# RealTimeClock.net
KiCad netlist of a schematic drawn in Altium Designer
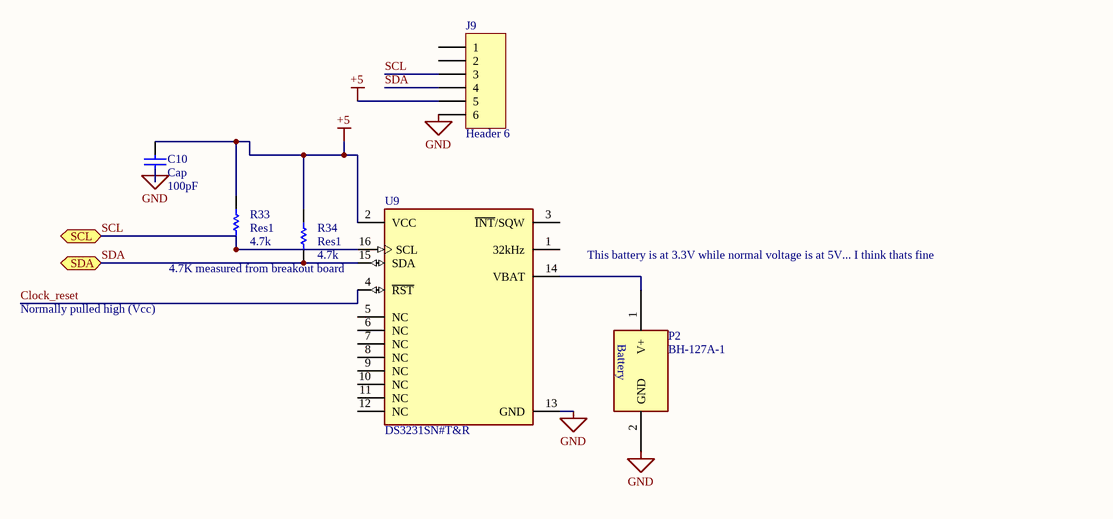
[diagram p0: RealTimeClock.SchDoc]

(export (version "E")
  (design (tool "Eeschema 10.0.6"))
  (components
    (comp (ref "C10")
      (value "Cap")
      (footprint "0603")
      (description "Capacitor")
      (fields (field (name "ALTIUM_VALUE") "100pF") (field (name "PUBLISHER") "Altium Limited"))
      (libsource (lib "Miscellaneous Devices") (part "Cap"))
    )
    (comp (ref "J9")
      (value "Header 6")
      (footprint "HDR1X6")
      (description "Header, 6-Pin")
      (fields (field (name "PUBLISHER") "Altium Limited"))
      (libsource (lib "Miscellaneous Connectors") (part "Header 6"))
    )
    (comp (ref "P2")
      (value "BH-127A-1")
      (footprint "banana")
      (libsource (lib "BH-127A-1") (part "BH-127A-1"))
    )
    (comp (ref "R33")
      (value "Res1")
      (footprint "0603")
      (description "Resistor")
      (fields (field (name "ALTIUM_VALUE") "4.7k") (field (name "PUBLISHER") "Altium Limited"))
      (libsource (lib "Miscellaneous Devices") (part "Res1"))
    )
    (comp (ref "R34")
      (value "Res1")
      (footprint "0603")
      (description "Resistor")
      (fields (field (name "ALTIUM_VALUE") "4.7k") (field (name "PUBLISHER") "Altium Limited"))
      (libsource (lib "Miscellaneous Devices") (part "Res1"))
    )
    (comp (ref "U9")
      (value "DS3231SN#T&R")
      (footprint "FP-W16-H2-MFG")
      (description "IC RTC CLK/CALENDAR I2C 16-SOIC")
      (libsource (lib "Altium Content Vault") (part "49e129a02c1e013a88f81c98964c20e"))
    )
  )
  (nets
    (net (code "1") (name "+5") (class "Default")
      (node (ref "C10") (pin "2") (pinfunction "2_2") (pintype "passive"))
      (node (ref "J9") (pin "5") (pinfunction "5_5") (pintype "passive"))
      (node (ref "R33") (pin "2") (pinfunction "2_2") (pintype "passive"))
      (node (ref "R34") (pin "2") (pinfunction "2_2") (pintype "passive"))
      (node (ref "U9") (pin "2") (pinfunction "VCC_2") (pintype "power_in"))
    )
    (net (code "2") (name "/Clock_reset") (class "Default")
      (node (ref "U9") (pin "4") (pinfunction "~{RST}_4") (pintype "bidirectional"))
    )
    (net (code "3") (name "/SCL") (class "Default")
      (node (ref "J9") (pin "3") (pinfunction "3_3") (pintype "passive"))
      (node (ref "R33") (pin "1") (pinfunction "1_1") (pintype "passive"))
      (node (ref "U9") (pin "16") (pinfunction "SCL_16") (pintype "input"))
    )
    (net (code "4") (name "/SDA") (class "Default")
      (node (ref "J9") (pin "4") (pinfunction "4_4") (pintype "passive"))
      (node (ref "R34") (pin "1") (pinfunction "1_1") (pintype "passive"))
      (node (ref "U9") (pin "15") (pinfunction "SDA_15") (pintype "bidirectional"))
    )
    (net (code "5") (name "GND") (class "Default")
      (node (ref "C10") (pin "1") (pinfunction "1_1") (pintype "passive"))
      (node (ref "J9") (pin "6") (pinfunction "6_6") (pintype "passive"))
      (node (ref "P2") (pin "2") (pinfunction "GND_2") (pintype "power_in"))
      (node (ref "U9") (pin "13") (pinfunction "GND_13") (pintype "power_in"))
    )
    (net (code "6") (name "Net-(P2-V+)") (class "Default")
      (node (ref "P2") (pin "1") (pinfunction "V+_1") (pintype "power_in"))
      (node (ref "U9") (pin "14") (pinfunction "VBAT_14") (pintype "power_in"))
    )
    (net (code "7") (name "unconnected-(J9-Pad1)") (class "Default")
      (node (ref "J9") (pin "1") (pinfunction "1_1") (pintype "passive"))
    )
    (net (code "8") (name "unconnected-(J9-Pad2)") (class "Default")
      (node (ref "J9") (pin "2") (pinfunction "2_2") (pintype "passive"))
    )
    (net (code "9") (name "unconnected-(U9-32kHz-Pad1)") (class "Default")
      (node (ref "U9") (pin "1") (pinfunction "32kHz_1") (pintype "open_collector"))
    )
    (net (code "10") (name "unconnected-(U9-NC-Pad5)") (class "Default")
      (node (ref "U9") (pin "5") (pinfunction "NC_5") (pintype "passive"))
    )
    (net (code "11") (name "unconnected-(U9-NC-Pad6)") (class "Default")
      (node (ref "U9") (pin "6") (pinfunction "NC_6") (pintype "passive"))
    )
    (net (code "12") (name "unconnected-(U9-NC-Pad7)") (class "Default")
      (node (ref "U9") (pin "7") (pinfunction "NC_7") (pintype "passive"))
    )
    (net (code "13") (name "unconnected-(U9-NC-Pad8)") (class "Default")
      (node (ref "U9") (pin "8") (pinfunction "NC_8") (pintype "passive"))
    )
    (net (code "14") (name "unconnected-(U9-NC-Pad9)") (class "Default")
      (node (ref "U9") (pin "9") (pinfunction "NC_9") (pintype "passive"))
    )
    (net (code "15") (name "unconnected-(U9-NC-Pad10)") (class "Default")
      (node (ref "U9") (pin "10") (pinfunction "NC_10") (pintype "passive"))
    )
    (net (code "16") (name "unconnected-(U9-NC-Pad11)") (class "Default")
      (node (ref "U9") (pin "11") (pinfunction "NC_11") (pintype "passive"))
    )
    (net (code "17") (name "unconnected-(U9-NC-Pad12)") (class "Default")
      (node (ref "U9") (pin "12") (pinfunction "NC_12") (pintype "passive"))
    )
    (net (code "18") (name "unconnected-(U9-~{INT}{slash}SQW-Pad3)") (class "Default")
      (node (ref "U9") (pin "3") (pinfunction "~{INT}/SQW_3") (pintype "open_collector"))
    )
  )
)
